# untitled.net
KiCad netlist of a schematic drawn in EAGLE
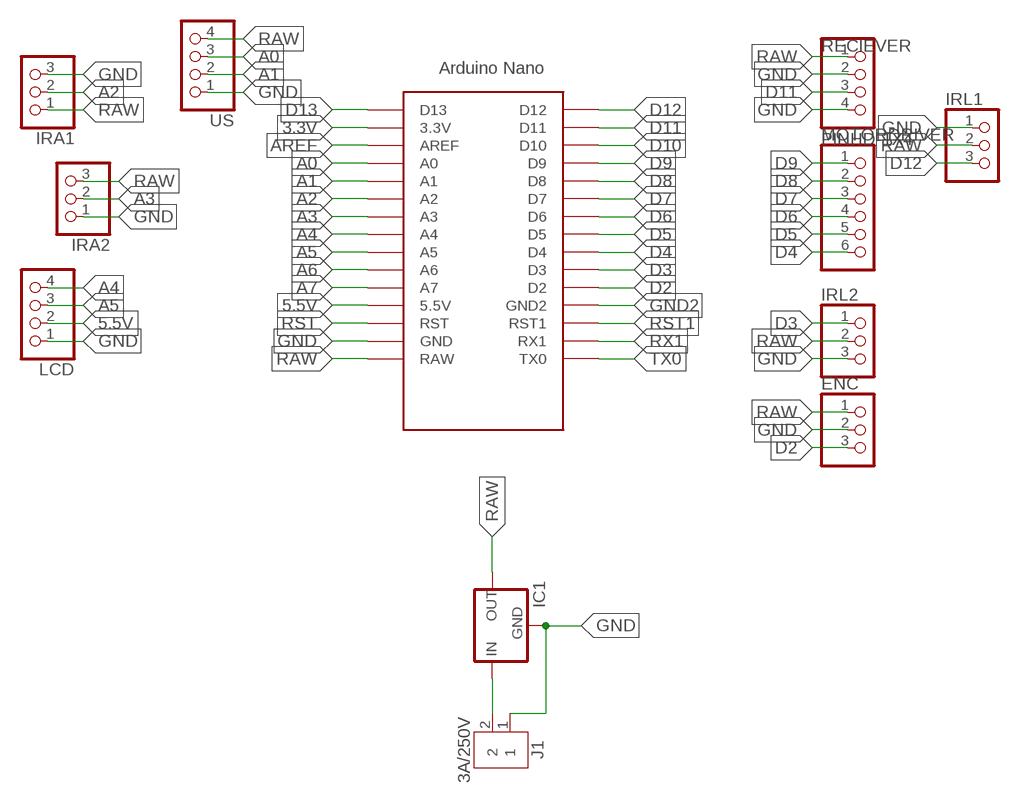
[diagram p0: schematic, sheet 1]

(export (version "E")
  (design (tool "Eeschema 10.0.6"))
  (components
    (comp (ref "ENC")
      (value "PINHD-1X3")
      (footprint "eagle-import:1X03")
      (libsource (lib "eagle-import") (part "PINHD-1X3"))
    )
    (comp (ref "IC1")
      (value "78XXS")
      (footprint "eagle-import:78XXS")
      (libsource (lib "eagle-import") (part "78XXS"))
    )
    (comp (ref "IRA1")
      (value "PINHD-1X3")
      (footprint "eagle-import:1X03")
      (libsource (lib "eagle-import") (part "PINHD-1X3"))
    )
    (comp (ref "IRA2")
      (value "PINHD-1X3")
      (footprint "eagle-import:1X03")
      (libsource (lib "eagle-import") (part "PINHD-1X3"))
    )
    (comp (ref "IRL1")
      (value "PINHD-1X3")
      (footprint "eagle-import:1X03")
      (libsource (lib "eagle-import") (part "PINHD-1X3"))
    )
    (comp (ref "IRL2")
      (value "PINHD-1X3")
      (footprint "eagle-import:1X03")
      (libsource (lib "eagle-import") (part "PINHD-1X3"))
    )
    (comp (ref "J1")
      (value "3A/250V")
      (footprint "eagle-import:B2B-XH-A")
      (fields (field (name "MANUFACTURER") "JST (XH CONNECTOR)") (field (name "MPN") "B2B-XH-A"))
      (libsource (lib "eagle-import") (part "B2B-XH-A"))
    )
    (comp (ref "LCD")
      (value "PINHD-1X4")
      (footprint "eagle-import:1X04")
      (libsource (lib "eagle-import") (part "MIA-Training_PINHD-1X4"))
    )
    (comp (ref "MOTORDRIVER")
      (value "PINHD-1X6")
      (footprint "eagle-import:1X06")
      (libsource (lib "eagle-import") (part "PINHD-1X6"))
    )
    (comp (ref "RECIEVER")
      (value "PINHD-1X4")
      (footprint "eagle-import:1X04")
      (libsource (lib "eagle-import") (part "PINHD-1X4"))
    )
    (comp (ref "U$1")
      (value "ARDUINO_NANO")
      (footprint "eagle-import:NANO")
      (libsource (lib "eagle-import") (part "ARDUINO_NANO"))
    )
    (comp (ref "US")
      (value "PINHD-1X4")
      (footprint "eagle-import:1X04")
      (libsource (lib "eagle-import") (part "MIA-Training_PINHD-1X4"))
    )
  )
  (nets
    (net (code "1") (name "3.3V") (class "Default")
      (node (ref "U$1") (pin "3.3V") (pinfunction "3.3V_3.3V") (pintype "bidirectional"))
    )
    (net (code "2") (name "5.5V") (class "Default")
      (node (ref "LCD") (pin "2") (pinfunction "2_2") (pintype "passive"))
      (node (ref "U$1") (pin "5V") (pinfunction "5.5V_5V") (pintype "bidirectional"))
    )
    (net (code "3") (name "A0") (class "Default")
      (node (ref "U$1") (pin "A0") (pinfunction "A0_A0") (pintype "bidirectional"))
      (node (ref "US") (pin "3") (pinfunction "3_3") (pintype "passive"))
    )
    (net (code "4") (name "A1") (class "Default")
      (node (ref "U$1") (pin "A1") (pinfunction "A1_A1") (pintype "bidirectional"))
      (node (ref "US") (pin "2") (pinfunction "2_2") (pintype "passive"))
    )
    (net (code "5") (name "A2") (class "Default")
      (node (ref "IRA1") (pin "2") (pinfunction "2_2") (pintype "passive"))
      (node (ref "U$1") (pin "A2") (pinfunction "A2_A2") (pintype "bidirectional"))
    )
    (net (code "6") (name "A3") (class "Default")
      (node (ref "IRA2") (pin "2") (pinfunction "2_2") (pintype "passive"))
      (node (ref "U$1") (pin "A3") (pinfunction "A3_A3") (pintype "bidirectional"))
    )
    (net (code "7") (name "A4") (class "Default")
      (node (ref "LCD") (pin "4") (pinfunction "4_4") (pintype "passive"))
      (node (ref "U$1") (pin "A4") (pinfunction "A4_A4") (pintype "bidirectional"))
    )
    (net (code "8") (name "A5") (class "Default")
      (node (ref "LCD") (pin "3") (pinfunction "3_3") (pintype "passive"))
      (node (ref "U$1") (pin "A5") (pinfunction "A5_A5") (pintype "bidirectional"))
    )
    (net (code "9") (name "A6") (class "Default")
      (node (ref "U$1") (pin "A6") (pinfunction "A6_A6") (pintype "bidirectional"))
    )
    (net (code "10") (name "A7") (class "Default")
      (node (ref "U$1") (pin "A7") (pinfunction "A7_A7") (pintype "bidirectional"))
    )
    (net (code "11") (name "AREF") (class "Default")
      (node (ref "U$1") (pin "AREF") (pinfunction "AREF_AREF") (pintype "bidirectional"))
    )
    (net (code "12") (name "D2") (class "Default")
      (node (ref "ENC") (pin "3") (pinfunction "3_3") (pintype "passive"))
      (node (ref "U$1") (pin "D2") (pinfunction "D2_D2") (pintype "bidirectional"))
    )
    (net (code "13") (name "D3") (class "Default")
      (node (ref "IRL2") (pin "1") (pinfunction "1_1") (pintype "passive"))
      (node (ref "U$1") (pin "D3") (pinfunction "D3_D3") (pintype "bidirectional"))
    )
    (net (code "14") (name "D4") (class "Default")
      (node (ref "MOTORDRIVER") (pin "6") (pinfunction "6_6") (pintype "passive"))
      (node (ref "U$1") (pin "D4") (pinfunction "D4_D4") (pintype "bidirectional"))
    )
    (net (code "15") (name "D5") (class "Default")
      (node (ref "MOTORDRIVER") (pin "5") (pinfunction "5_5") (pintype "passive"))
      (node (ref "U$1") (pin "D5") (pinfunction "D5_D5") (pintype "bidirectional"))
    )
    (net (code "16") (name "D6") (class "Default")
      (node (ref "MOTORDRIVER") (pin "4") (pinfunction "4_4") (pintype "passive"))
      (node (ref "U$1") (pin "D6") (pinfunction "D6_D6") (pintype "bidirectional"))
    )
    (net (code "17") (name "D7") (class "Default")
      (node (ref "MOTORDRIVER") (pin "3") (pinfunction "3_3") (pintype "passive"))
      (node (ref "U$1") (pin "D7") (pinfunction "D7_D7") (pintype "bidirectional"))
    )
    (net (code "18") (name "D8") (class "Default")
      (node (ref "MOTORDRIVER") (pin "2") (pinfunction "2_2") (pintype "passive"))
      (node (ref "U$1") (pin "D8") (pinfunction "D8_D8") (pintype "bidirectional"))
    )
    (net (code "19") (name "D9") (class "Default")
      (node (ref "MOTORDRIVER") (pin "1") (pinfunction "1_1") (pintype "passive"))
      (node (ref "U$1") (pin "D9") (pinfunction "D9_D9") (pintype "bidirectional"))
    )
    (net (code "20") (name "D10") (class "Default")
      (node (ref "U$1") (pin "D10") (pinfunction "D10_D10") (pintype "bidirectional"))
    )
    (net (code "21") (name "D11") (class "Default")
      (node (ref "RECIEVER") (pin "3") (pinfunction "3_3") (pintype "passive"))
      (node (ref "U$1") (pin "D11") (pinfunction "D11_D11") (pintype "bidirectional"))
    )
    (net (code "22") (name "D12") (class "Default")
      (node (ref "IRL1") (pin "3") (pinfunction "3_3") (pintype "passive"))
      (node (ref "U$1") (pin "D12") (pinfunction "D12_D12") (pintype "bidirectional"))
    )
    (net (code "23") (name "D13") (class "Default")
      (node (ref "U$1") (pin "D13") (pinfunction "D13_D13") (pintype "bidirectional"))
    )
    (net (code "24") (name "GND") (class "Default")
      (node (ref "ENC") (pin "2") (pinfunction "2_2") (pintype "passive"))
      (node (ref "IC1") (pin "GND") (pinfunction "GND_GND") (pintype "input"))
      (node (ref "IRA1") (pin "3") (pinfunction "3_3") (pintype "passive"))
      (node (ref "IRA2") (pin "1") (pinfunction "1_1") (pintype "passive"))
      (node (ref "IRL1") (pin "1") (pinfunction "1_1") (pintype "passive"))
      (node (ref "IRL2") (pin "3") (pinfunction "3_3") (pintype "passive"))
      (node (ref "J1") (pin "1") (pinfunction "1_1") (pintype "bidirectional"))
      (node (ref "LCD") (pin "1") (pinfunction "1_1") (pintype "passive"))
      (node (ref "RECIEVER") (pin "2") (pinfunction "2_2") (pintype "passive"))
      (node (ref "RECIEVER") (pin "4") (pinfunction "4_4") (pintype "passive"))
      (node (ref "U$1") (pin "GND") (pinfunction "GND_GND") (pintype "bidirectional"))
      (node (ref "US") (pin "1") (pinfunction "1_1") (pintype "passive"))
    )
    (net (code "25") (name "GND2") (class "Default")
      (node (ref "U$1") (pin "GND1") (pinfunction "GND2_GND1") (pintype "bidirectional"))
    )
    (net (code "26") (name "Net-(IC1-PadIN)") (class "Default")
      (node (ref "IC1") (pin "IN") (pinfunction "IN_IN") (pintype "input"))
      (node (ref "J1") (pin "2") (pinfunction "2_2") (pintype "bidirectional"))
    )
    (net (code "27") (name "RAW") (class "Default")
      (node (ref "ENC") (pin "1") (pinfunction "1_1") (pintype "passive"))
      (node (ref "IC1") (pin "OUT") (pinfunction "OUT_OUT") (pintype "passive"))
      (node (ref "IRA1") (pin "1") (pinfunction "1_1") (pintype "passive"))
      (node (ref "IRA2") (pin "3") (pinfunction "3_3") (pintype "passive"))
      (node (ref "IRL1") (pin "2") (pinfunction "2_2") (pintype "passive"))
      (node (ref "IRL2") (pin "2") (pinfunction "2_2") (pintype "passive"))
      (node (ref "RECIEVER") (pin "1") (pinfunction "1_1") (pintype "passive"))
      (node (ref "U$1") (pin "RAW") (pinfunction "RAW_RAW") (pintype "bidirectional"))
      (node (ref "US") (pin "4") (pinfunction "4_4") (pintype "passive"))
    )
    (net (code "28") (name "RST") (class "Default")
      (node (ref "U$1") (pin "RST") (pinfunction "RST_RST") (pintype "bidirectional"))
    )
    (net (code "29") (name "RST1") (class "Default")
      (node (ref "U$1") (pin "RST1") (pinfunction "RST1_RST1") (pintype "bidirectional"))
    )
    (net (code "30") (name "RX1") (class "Default")
      (node (ref "U$1") (pin "RX1") (pinfunction "RX1_RX1") (pintype "bidirectional"))
    )
    (net (code "31") (name "TX0") (class "Default")
      (node (ref "U$1") (pin "TX0") (pinfunction "TX0_TX0") (pintype "bidirectional"))
    )
  )
)
